# Peripheral.net
KiCad netlist of a schematic drawn in Altium Designer
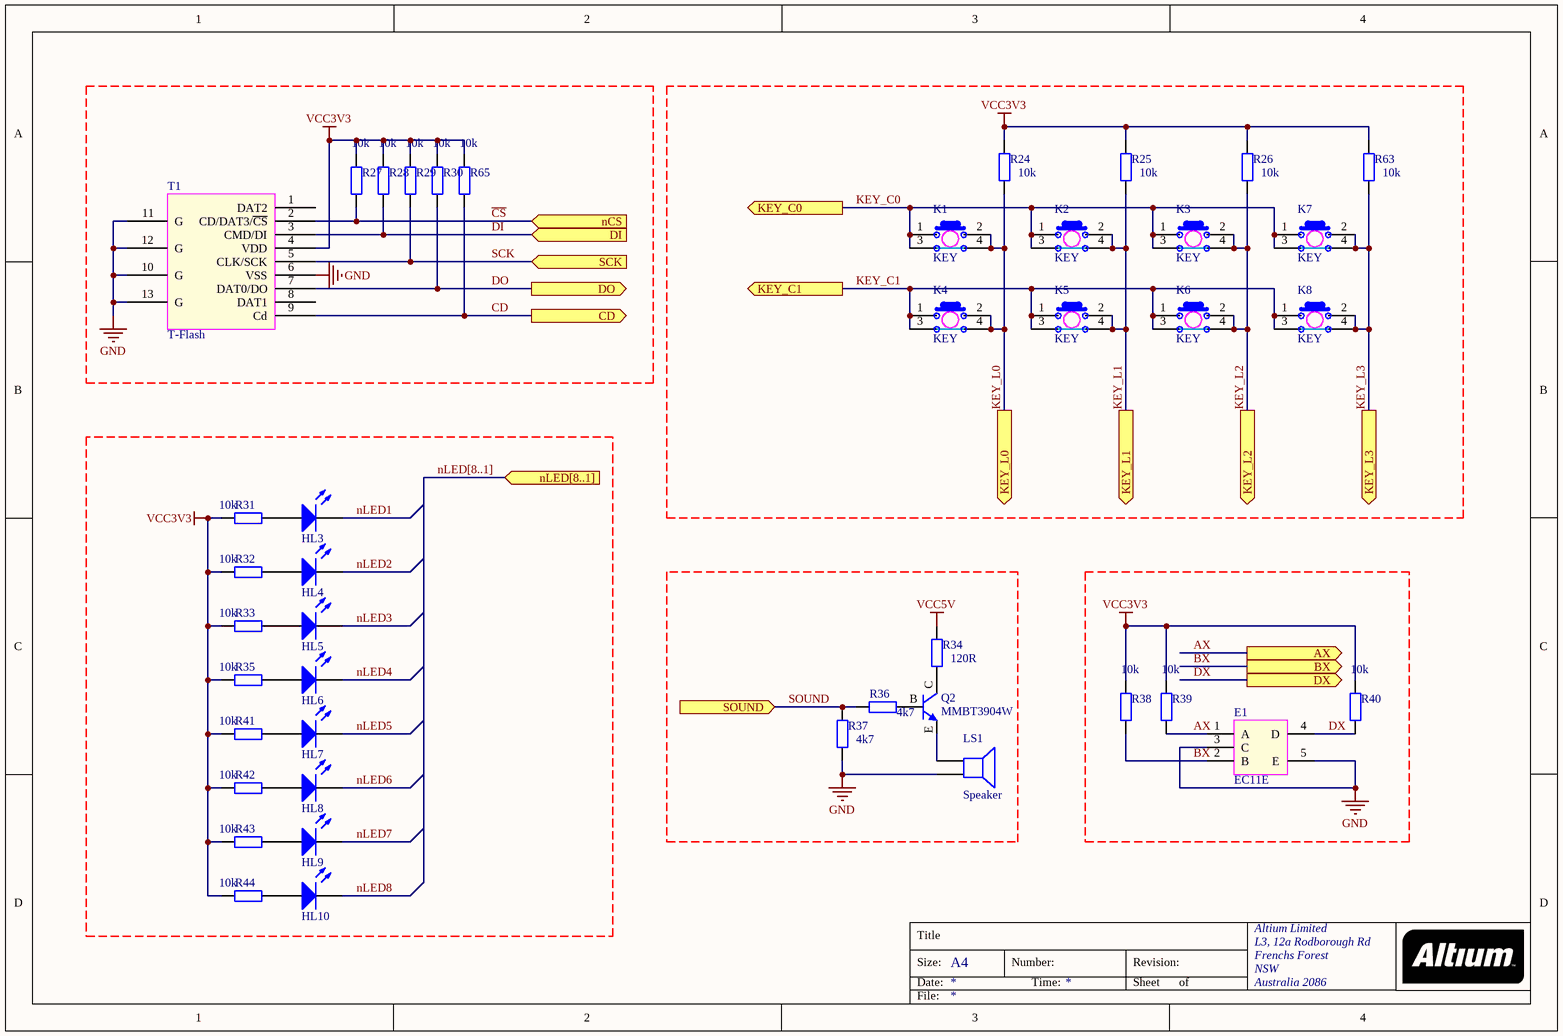
[diagram p0: Peripheral.SchDoc]

(export (version "E")
  (design (tool "Eeschema 10.0.6"))
  (components
    (comp (ref "E1")
      (value "EC11E")
      (footprint "EC11E")
      (description "encoder")
      (libsource (lib "MyYX") (part "EC11E"))
    )
    (comp (ref "HL3") (value "LED") (footprint "LED_0603") (libsource (lib "MyYX") (part "LED 2")))
    (comp (ref "HL4") (value "LED") (footprint "LED_0603") (libsource (lib "MyYX") (part "LED 2")))
    (comp (ref "HL5") (value "LED") (footprint "LED_0603") (libsource (lib "MyYX") (part "LED 2")))
    (comp (ref "HL6") (value "LED") (footprint "LED_0603") (libsource (lib "MyYX") (part "LED 2")))
    (comp (ref "HL7") (value "LED") (footprint "LED_0603") (libsource (lib "MyYX") (part "LED 2")))
    (comp (ref "HL8") (value "LED") (footprint "LED_0603") (libsource (lib "MyYX") (part "LED 2")))
    (comp (ref "HL9") (value "LED") (footprint "LED_0603") (libsource (lib "MyYX") (part "LED 2")))
    (comp (ref "HL10") (value "LED") (footprint "LED_0603") (libsource (lib "MyYX") (part "LED 2")))
    (comp (ref "K1") (value "KEY") (libsource (lib "MyYX") (part "KEY")))
    (comp (ref "K2") (value "KEY") (libsource (lib "MyYX") (part "KEY")))
    (comp (ref "K3") (value "KEY") (libsource (lib "MyYX") (part "KEY")))
    (comp (ref "K4") (value "KEY") (libsource (lib "MyYX") (part "KEY")))
    (comp (ref "K5") (value "KEY") (libsource (lib "MyYX") (part "KEY")))
    (comp (ref "K6") (value "KEY") (libsource (lib "MyYX") (part "KEY")))
    (comp (ref "K7") (value "KEY") (footprint "KEY3") (libsource (lib "MyYX") (part "KEY")))
    (comp (ref "K8") (value "KEY") (footprint "KEY3") (libsource (lib "MyYX") (part "KEY")))
    (comp (ref "LS1")
      (value "Speaker")
      (footprint "SPK1")
      (description "Loudspeaker")
      (fields (field (name "PUBLISHER") "Altium Limited"))
      (libsource (lib "Miscellaneous Devices") (part "Speaker"))
    )
    (comp (ref "Q2") (value "MMBT3904W") (footprint "SOT_23") (libsource (lib "MyYX") (part "MMBT3904TT1G")))
    (comp (ref "R24") (value "10k") (footprint "R0603") (libsource (lib "") (part "RES_04_1")))
    (comp (ref "R25") (value "10k") (footprint "R0603") (libsource (lib "") (part "RES_04_1")))
    (comp (ref "R26") (value "10k") (footprint "R0603") (libsource (lib "") (part "RES_04_1")))
    (comp (ref "R27") (value "10k") (footprint "R0603") (libsource (lib "") (part "RES_04_1")))
    (comp (ref "R28") (value "10k") (footprint "R0603") (libsource (lib "") (part "RES_04_1")))
    (comp (ref "R29") (value "10k") (footprint "R0603") (libsource (lib "") (part "RES_04_1")))
    (comp (ref "R30") (value "10k") (footprint "R0603") (libsource (lib "") (part "RES_04_1")))
    (comp (ref "R31") (value "10k") (footprint "R0603") (libsource (lib "MyYX") (part "RES_04")))
    (comp (ref "R32") (value "10k") (footprint "R0603") (libsource (lib "MyYX") (part "RES_04")))
    (comp (ref "R33") (value "10k") (footprint "R0603") (libsource (lib "MyYX") (part "RES_04")))
    (comp (ref "R34") (value "120R") (footprint "R0603") (libsource (lib "") (part "RES_04_2")))
    (comp (ref "R35") (value "10k") (footprint "R0603") (libsource (lib "MyYX") (part "RES_04")))
    (comp (ref "R36") (value "4k7") (footprint "R0603") (libsource (lib "MyYX") (part "RES_04")))
    (comp (ref "R37") (value "4k7") (footprint "R0603") (libsource (lib "") (part "RES_04_2")))
    (comp (ref "R38") (value "10k") (footprint "R0603") (libsource (lib "") (part "RES_04_1")))
    (comp (ref "R39") (value "10k") (footprint "R0603") (libsource (lib "") (part "RES_04_1")))
    (comp (ref "R40") (value "10k") (footprint "R0603") (libsource (lib "") (part "RES_04_1")))
    (comp (ref "R41") (value "10k") (footprint "R0603") (libsource (lib "MyYX") (part "RES_04")))
    (comp (ref "R42") (value "10k") (footprint "R0603") (libsource (lib "MyYX") (part "RES_04")))
    (comp (ref "R43") (value "10k") (footprint "R0603") (libsource (lib "MyYX") (part "RES_04")))
    (comp (ref "R44") (value "10k") (footprint "R0603") (libsource (lib "MyYX") (part "RES_04")))
    (comp (ref "R63") (value "10k") (footprint "R0603") (libsource (lib "") (part "RES_04_1")))
    (comp (ref "R65") (value "10k") (footprint "R0603") (libsource (lib "") (part "RES_04_1")))
    (comp (ref "T1")
      (value "T-Flash")
      (footprint "Micro-SD")
      (description "MICRO SD")
      (libsource (lib "MyYX") (part "T-Flash"))
    )
  )
  (nets
    (net (code "1") (name "/AX") (class "Default")
      (node (ref "E1") (pin "1") (pinfunction "A_1") (pintype "passive"))
      (node (ref "R39") (pin "1") (pinfunction "1_1") (pintype "passive"))
    )
    (net (code "2") (name "/BX") (class "Default")
      (node (ref "E1") (pin "2") (pinfunction "B_2") (pintype "passive"))
      (node (ref "R38") (pin "1") (pinfunction "1_1") (pintype "passive"))
    )
    (net (code "3") (name "/CD") (class "Default")
      (node (ref "R65") (pin "1") (pinfunction "1_1") (pintype "passive"))
      (node (ref "T1") (pin "9") (pinfunction "Cd_9") (pintype "passive"))
    )
    (net (code "4") (name "/DI") (class "Default")
      (node (ref "R28") (pin "1") (pinfunction "1_1") (pintype "passive"))
      (node (ref "T1") (pin "3") (pinfunction "CMD/DI_3") (pintype "passive"))
    )
    (net (code "5") (name "/DO") (class "Default")
      (node (ref "R30") (pin "1") (pinfunction "1_1") (pintype "passive"))
      (node (ref "T1") (pin "7") (pinfunction "DAT0/DO_7") (pintype "passive"))
    )
    (net (code "6") (name "/DX") (class "Default")
      (node (ref "E1") (pin "4") (pinfunction "D_4") (pintype "passive"))
      (node (ref "R40") (pin "1") (pinfunction "1_1") (pintype "passive"))
    )
    (net (code "7") (name "/KEY_C0") (class "Default")
      (node (ref "K1") (pin "1") (pinfunction "1_1") (pintype "passive"))
      (node (ref "K1") (pin "3") (pinfunction "3_3") (pintype "passive"))
      (node (ref "K2") (pin "1") (pinfunction "1_1") (pintype "passive"))
      (node (ref "K2") (pin "3") (pinfunction "3_3") (pintype "passive"))
      (node (ref "K3") (pin "1") (pinfunction "1_1") (pintype "passive"))
      (node (ref "K3") (pin "3") (pinfunction "3_3") (pintype "passive"))
      (node (ref "K7") (pin "1") (pinfunction "1_1") (pintype "passive"))
      (node (ref "K7") (pin "3") (pinfunction "3_3") (pintype "passive"))
    )
    (net (code "8") (name "/KEY_C1") (class "Default")
      (node (ref "K4") (pin "1") (pinfunction "1_1") (pintype "passive"))
      (node (ref "K4") (pin "3") (pinfunction "3_3") (pintype "passive"))
      (node (ref "K5") (pin "1") (pinfunction "1_1") (pintype "passive"))
      (node (ref "K5") (pin "3") (pinfunction "3_3") (pintype "passive"))
      (node (ref "K6") (pin "1") (pinfunction "1_1") (pintype "passive"))
      (node (ref "K6") (pin "3") (pinfunction "3_3") (pintype "passive"))
      (node (ref "K8") (pin "1") (pinfunction "1_1") (pintype "passive"))
      (node (ref "K8") (pin "3") (pinfunction "3_3") (pintype "passive"))
    )
    (net (code "9") (name "/KEY_L0") (class "Default")
      (node (ref "K1") (pin "2") (pinfunction "2_2") (pintype "passive"))
      (node (ref "K1") (pin "4") (pinfunction "4_4") (pintype "passive"))
      (node (ref "K4") (pin "2") (pinfunction "2_2") (pintype "passive"))
      (node (ref "K4") (pin "4") (pinfunction "4_4") (pintype "passive"))
      (node (ref "R24") (pin "1") (pinfunction "1_1") (pintype "passive"))
    )
    (net (code "10") (name "/KEY_L1") (class "Default")
      (node (ref "K2") (pin "2") (pinfunction "2_2") (pintype "passive"))
      (node (ref "K2") (pin "4") (pinfunction "4_4") (pintype "passive"))
      (node (ref "K5") (pin "2") (pinfunction "2_2") (pintype "passive"))
      (node (ref "K5") (pin "4") (pinfunction "4_4") (pintype "passive"))
      (node (ref "R25") (pin "1") (pinfunction "1_1") (pintype "passive"))
    )
    (net (code "11") (name "/KEY_L2") (class "Default")
      (node (ref "K3") (pin "2") (pinfunction "2_2") (pintype "passive"))
      (node (ref "K3") (pin "4") (pinfunction "4_4") (pintype "passive"))
      (node (ref "K6") (pin "2") (pinfunction "2_2") (pintype "passive"))
      (node (ref "K6") (pin "4") (pinfunction "4_4") (pintype "passive"))
      (node (ref "R26") (pin "1") (pinfunction "1_1") (pintype "passive"))
    )
    (net (code "12") (name "/KEY_L3") (class "Default")
      (node (ref "K7") (pin "2") (pinfunction "2_2") (pintype "passive"))
      (node (ref "K7") (pin "4") (pinfunction "4_4") (pintype "passive"))
      (node (ref "K8") (pin "2") (pinfunction "2_2") (pintype "passive"))
      (node (ref "K8") (pin "4") (pinfunction "4_4") (pintype "passive"))
      (node (ref "R63") (pin "1") (pinfunction "1_1") (pintype "passive"))
    )
    (net (code "13") (name "/SCK") (class "Default")
      (node (ref "R29") (pin "1") (pinfunction "1_1") (pintype "passive"))
      (node (ref "T1") (pin "5") (pinfunction "CLK/SCK_5") (pintype "passive"))
    )
    (net (code "14") (name "/SOUND") (class "Default")
      (node (ref "R36") (pin "2") (pinfunction "2_2") (pintype "passive"))
      (node (ref "R37") (pin "1") (pinfunction "1_1") (pintype "passive"))
    )
    (net (code "15") (name "/nLED1") (class "Default")
      (node (ref "HL3") (pin "K") (pinfunction "2_K") (pintype "passive"))
    )
    (net (code "16") (name "/nLED2") (class "Default")
      (node (ref "HL4") (pin "K") (pinfunction "2_K") (pintype "passive"))
    )
    (net (code "17") (name "/nLED3") (class "Default")
      (node (ref "HL5") (pin "K") (pinfunction "2_K") (pintype "passive"))
    )
    (net (code "18") (name "/nLED4") (class "Default")
      (node (ref "HL6") (pin "K") (pinfunction "2_K") (pintype "passive"))
    )
    (net (code "19") (name "/nLED5") (class "Default")
      (node (ref "HL7") (pin "K") (pinfunction "2_K") (pintype "passive"))
    )
    (net (code "20") (name "/nLED6") (class "Default")
      (node (ref "HL8") (pin "K") (pinfunction "2_K") (pintype "passive"))
    )
    (net (code "21") (name "/nLED7") (class "Default")
      (node (ref "HL9") (pin "K") (pinfunction "2_K") (pintype "passive"))
    )
    (net (code "22") (name "/nLED8") (class "Default")
      (node (ref "HL10") (pin "K") (pinfunction "2_K") (pintype "passive"))
    )
    (net (code "24") (name "/~{CS}") (class "Default")
      (node (ref "R27") (pin "1") (pinfunction "1_1") (pintype "passive"))
      (node (ref "T1") (pin "2") (pinfunction "CD/DAT3/~{CS}_2") (pintype "passive"))
    )
    (net (code "25") (name "GND") (class "Default")
      (node (ref "E1") (pin "3") (pinfunction "C_3") (pintype "passive"))
      (node (ref "E1") (pin "5") (pinfunction "E_5") (pintype "passive"))
      (node (ref "LS1") (pin "2") (pinfunction "2_2") (pintype "passive"))
      (node (ref "R37") (pin "2") (pinfunction "2_2") (pintype "passive"))
      (node (ref "T1") (pin "10") (pinfunction "G_10") (pintype "passive"))
      (node (ref "T1") (pin "11") (pinfunction "G_11") (pintype "passive"))
      (node (ref "T1") (pin "12") (pinfunction "G_12") (pintype "passive"))
      (node (ref "T1") (pin "13") (pinfunction "G_13") (pintype "passive"))
      (node (ref "T1") (pin "6") (pinfunction "VSS_6") (pintype "passive"))
    )
    (net (code "26") (name "Net-(HL3-1)") (class "Default")
      (node (ref "HL3") (pin "A") (pinfunction "1_A") (pintype "passive"))
      (node (ref "R31") (pin "1") (pinfunction "1_1") (pintype "passive"))
    )
    (net (code "27") (name "Net-(HL4-1)") (class "Default")
      (node (ref "HL4") (pin "A") (pinfunction "1_A") (pintype "passive"))
      (node (ref "R32") (pin "1") (pinfunction "1_1") (pintype "passive"))
    )
    (net (code "28") (name "Net-(HL5-1)") (class "Default")
      (node (ref "HL5") (pin "A") (pinfunction "1_A") (pintype "passive"))
      (node (ref "R33") (pin "1") (pinfunction "1_1") (pintype "passive"))
    )
    (net (code "29") (name "Net-(HL6-1)") (class "Default")
      (node (ref "HL6") (pin "A") (pinfunction "1_A") (pintype "passive"))
      (node (ref "R35") (pin "1") (pinfunction "1_1") (pintype "passive"))
    )
    (net (code "30") (name "Net-(HL7-1)") (class "Default")
      (node (ref "HL7") (pin "A") (pinfunction "1_A") (pintype "passive"))
      (node (ref "R41") (pin "1") (pinfunction "1_1") (pintype "passive"))
    )
    (net (code "31") (name "Net-(HL8-1)") (class "Default")
      (node (ref "HL8") (pin "A") (pinfunction "1_A") (pintype "passive"))
      (node (ref "R42") (pin "1") (pinfunction "1_1") (pintype "passive"))
    )
    (net (code "32") (name "Net-(HL9-1)") (class "Default")
      (node (ref "HL9") (pin "A") (pinfunction "1_A") (pintype "passive"))
      (node (ref "R43") (pin "1") (pinfunction "1_1") (pintype "passive"))
    )
    (net (code "33") (name "Net-(HL10-1)") (class "Default")
      (node (ref "HL10") (pin "A") (pinfunction "1_A") (pintype "passive"))
      (node (ref "R44") (pin "1") (pinfunction "1_1") (pintype "passive"))
    )
    (net (code "34") (name "Net-(LS1-Pad1)") (class "Default")
      (node (ref "LS1") (pin "1") (pinfunction "1_1") (pintype "passive"))
      (node (ref "Q2") (pin "E") (pinfunction "E_E") (pintype "passive"))
    )
    (net (code "35") (name "Net-(Q2-PadB)") (class "Default")
      (node (ref "Q2") (pin "B") (pinfunction "B_B") (pintype "passive"))
      (node (ref "R36") (pin "1") (pinfunction "1_1") (pintype "passive"))
    )
    (net (code "36") (name "Net-(Q2-PadC)") (class "Default")
      (node (ref "Q2") (pin "C") (pinfunction "C_C") (pintype "passive"))
      (node (ref "R34") (pin "2") (pinfunction "2_2") (pintype "passive"))
    )
    (net (code "37") (name "VCC3V3") (class "Default")
      (node (ref "R24") (pin "2") (pinfunction "2_2") (pintype "passive"))
      (node (ref "R25") (pin "2") (pinfunction "2_2") (pintype "passive"))
      (node (ref "R26") (pin "2") (pinfunction "2_2") (pintype "passive"))
      (node (ref "R27") (pin "2") (pinfunction "2_2") (pintype "passive"))
      (node (ref "R28") (pin "2") (pinfunction "2_2") (pintype "passive"))
      (node (ref "R29") (pin "2") (pinfunction "2_2") (pintype "passive"))
      (node (ref "R30") (pin "2") (pinfunction "2_2") (pintype "passive"))
      (node (ref "R31") (pin "2") (pinfunction "2_2") (pintype "passive"))
      (node (ref "R32") (pin "2") (pinfunction "2_2") (pintype "passive"))
      (node (ref "R33") (pin "2") (pinfunction "2_2") (pintype "passive"))
      (node (ref "R35") (pin "2") (pinfunction "2_2") (pintype "passive"))
      (node (ref "R38") (pin "2") (pinfunction "2_2") (pintype "passive"))
      (node (ref "R39") (pin "2") (pinfunction "2_2") (pintype "passive"))
      (node (ref "R40") (pin "2") (pinfunction "2_2") (pintype "passive"))
      (node (ref "R41") (pin "2") (pinfunction "2_2") (pintype "passive"))
      (node (ref "R42") (pin "2") (pinfunction "2_2") (pintype "passive"))
      (node (ref "R43") (pin "2") (pinfunction "2_2") (pintype "passive"))
      (node (ref "R44") (pin "2") (pinfunction "2_2") (pintype "passive"))
      (node (ref "R63") (pin "2") (pinfunction "2_2") (pintype "passive"))
      (node (ref "R65") (pin "2") (pinfunction "2_2") (pintype "passive"))
      (node (ref "T1") (pin "4") (pinfunction "VDD_4") (pintype "passive"))
    )
    (net (code "38") (name "VCC5V") (class "Default")
      (node (ref "R34") (pin "1") (pinfunction "1_1") (pintype "passive"))
    )
    (net (code "39") (name "unconnected-(T1-DAT1-Pad8)") (class "Default")
      (node (ref "T1") (pin "8") (pinfunction "DAT1_8") (pintype "passive"))
    )
    (net (code "40") (name "unconnected-(T1-DAT2-Pad1)") (class "Default")
      (node (ref "T1") (pin "1") (pinfunction "DAT2_1") (pintype "passive"))
    )
  )
)
